# cw304_notduino_02.net
KiCad netlist of a schematic drawn in EAGLE
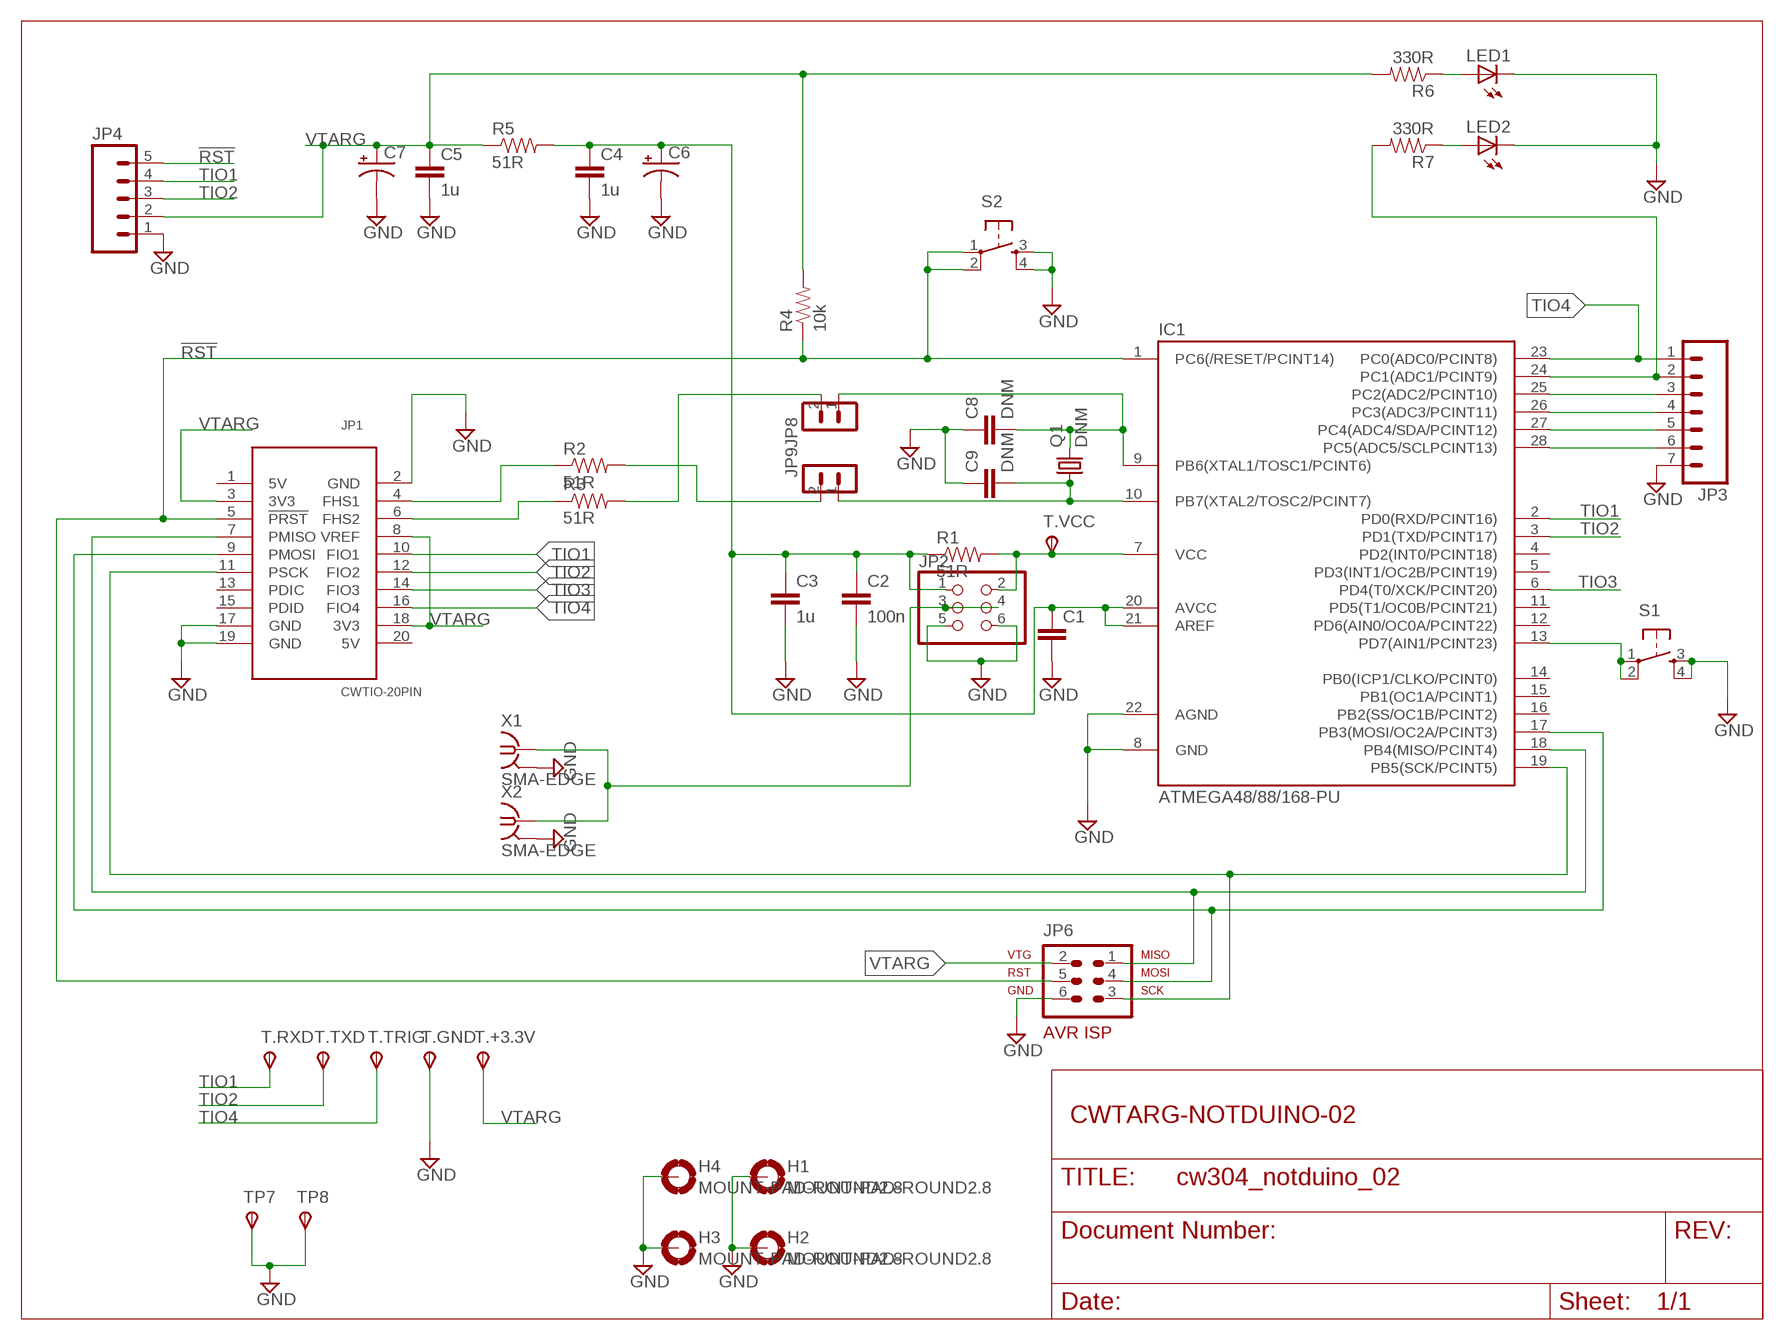
[diagram p0: schematic, sheet 1]

(export (version "E")
  (design (tool "Eeschema 10.0.6"))
  (components
    (comp (ref "C1")
      (value "CAPPTH")
      (footprint "eagle-import:CAP-PTH-SMALL")
      (libsource (lib "eagle-import") (part "CAPPTH"))
    )
    (comp (ref "C2")
      (value "100n")
      (footprint "eagle-import:CAP-PTH-SMALL")
      (libsource (lib "eagle-import") (part "CAPPTH"))
    )
    (comp (ref "C3")
      (value "1u")
      (footprint "eagle-import:CAP-PTH-SMALL")
      (libsource (lib "eagle-import") (part "CAPPTH"))
    )
    (comp (ref "C4")
      (value "1u")
      (footprint "eagle-import:CAP-PTH-SMALL")
      (libsource (lib "eagle-import") (part "CAPPTH"))
    )
    (comp (ref "C5")
      (value "1u")
      (footprint "eagle-import:CAP-PTH-SMALL")
      (libsource (lib "eagle-import") (part "CAPPTH"))
    )
    (comp (ref "C6")
      (value "CAP_POLPTH1")
      (footprint "eagle-import:CPOL-RADIAL-100UF-25V")
      (libsource (lib "eagle-import") (part "CAP_POLPTH1"))
    )
    (comp (ref "C7")
      (value "CAP_POLPTH1")
      (footprint "eagle-import:CPOL-RADIAL-100UF-25V")
      (libsource (lib "eagle-import") (part "CAP_POLPTH1"))
    )
    (comp (ref "C8")
      (value "DNM")
      (footprint "eagle-import:CAP-PTH-SMALL")
      (libsource (lib "eagle-import") (part "CAPPTH"))
    )
    (comp (ref "C9")
      (value "DNM")
      (footprint "eagle-import:CAP-PTH-SMALL")
      (libsource (lib "eagle-import") (part "CAPPTH"))
    )
    (comp (ref "H1")
      (value "MOUNT-PAD-ROUND2.8")
      (footprint "eagle-import:2,8-PAD")
      (libsource (lib "eagle-import") (part "MOUNT-PAD-ROUND2.8"))
    )
    (comp (ref "H2")
      (value "MOUNT-PAD-ROUND2.8")
      (footprint "eagle-import:2,8-PAD")
      (libsource (lib "eagle-import") (part "MOUNT-PAD-ROUND2.8"))
    )
    (comp (ref "H3")
      (value "MOUNT-PAD-ROUND2.8")
      (footprint "eagle-import:2,8-PAD")
      (libsource (lib "eagle-import") (part "MOUNT-PAD-ROUND2.8"))
    )
    (comp (ref "H4")
      (value "MOUNT-PAD-ROUND2.8")
      (footprint "eagle-import:2,8-PAD")
      (libsource (lib "eagle-import") (part "MOUNT-PAD-ROUND2.8"))
    )
    (comp (ref "IC1")
      (value "ATMEGA48/88/168-PU")
      (footprint "eagle-import:DIL28-3")
      (libsource (lib "eagle-import") (part "ATMEGA48/88/168-PU"))
    )
    (comp (ref "JP1")
      (value "CWTIO-20PIN")
      (footprint "eagle-import:PINSHRD_PTH_2X10")
      (libsource (lib "eagle-import") (part "CWTIO-20PIN"))
    )
    (comp (ref "JP2")
      (value "PINHD-2X3")
      (footprint "eagle-import:2X03")
      (libsource (lib "eagle-import") (part "PINHD-2X3"))
    )
    (comp (ref "JP3")
      (value "M07LOCK")
      (footprint "eagle-import:1X07_LOCK")
      (libsource (lib "eagle-import") (part "M07LOCK"))
    )
    (comp (ref "JP4")
      (value "M05LOCK")
      (footprint "eagle-import:1X05_LOCK")
      (libsource (lib "eagle-import") (part "M05LOCK"))
    )
    (comp (ref "JP6")
      (value "AVR-ISP-6")
      (footprint "eagle-import:AVR-ISP-6")
      (libsource (lib "eagle-import") (part "AVR-ISP-6"))
    )
    (comp (ref "JP8")
      (value "M02LOCK")
      (footprint "eagle-import:1X02_LOCK")
      (libsource (lib "eagle-import") (part "M02LOCK"))
    )
    (comp (ref "JP9")
      (value "M02LOCK")
      (footprint "eagle-import:1X02_LOCK")
      (libsource (lib "eagle-import") (part "M02LOCK"))
    )
    (comp (ref "LED1")
      (value "LED5MM")
      (footprint "eagle-import:LED5MM")
      (libsource (lib "eagle-import") (part "LED5MM"))
    )
    (comp (ref "LED2")
      (value "LED5MM")
      (footprint "eagle-import:LED5MM")
      (libsource (lib "eagle-import") (part "LED5MM"))
    )
    (comp (ref "Q1")
      (value "DNM")
      (footprint "eagle-import:HC49U-V")
      (libsource (lib "eagle-import") (part "CRYSTALHC49U-V"))
    )
    (comp (ref "R1")
      (value "51R")
      (footprint "eagle-import:AXIAL-0.4")
      (libsource (lib "eagle-import") (part "RESISTORPTH-1/4W"))
    )
    (comp (ref "R2")
      (value "51R")
      (footprint "eagle-import:AXIAL-0.4")
      (libsource (lib "eagle-import") (part "RESISTORPTH-1/4W"))
    )
    (comp (ref "R3")
      (value "51R")
      (footprint "eagle-import:AXIAL-0.4")
      (libsource (lib "eagle-import") (part "RESISTORPTH-1/4W"))
    )
    (comp (ref "R4")
      (value "10k")
      (footprint "eagle-import:AXIAL-0.4")
      (libsource (lib "eagle-import") (part "RESISTORPTH-1/4W"))
    )
    (comp (ref "R5")
      (value "51R")
      (footprint "eagle-import:AXIAL-0.4")
      (libsource (lib "eagle-import") (part "RESISTORPTH-1/4W"))
    )
    (comp (ref "R6")
      (value "330R")
      (footprint "eagle-import:AXIAL-0.4")
      (libsource (lib "eagle-import") (part "RESISTORPTH-1/4W"))
    )
    (comp (ref "R7")
      (value "330R")
      (footprint "eagle-import:AXIAL-0.4")
      (libsource (lib "eagle-import") (part "RESISTORPTH-1/4W"))
    )
    (comp (ref "S1")
      (value "TAC_SWITCHPTH")
      (footprint "eagle-import:TACTILE-PTH")
      (libsource (lib "eagle-import") (part "TAC_SWITCHPTH"))
    )
    (comp (ref "S2")
      (value "TAC_SWITCHPTH")
      (footprint "eagle-import:TACTILE-PTH")
      (libsource (lib "eagle-import") (part "TAC_SWITCHPTH"))
    )
    (comp (ref "T.+3.3V")
      (value "TPSPAD1-13")
      (footprint "eagle-import:P1-13")
      (libsource (lib "eagle-import") (part "TPSPAD1-13"))
    )
    (comp (ref "T.GND")
      (value "TPSPAD1-13")
      (footprint "eagle-import:P1-13")
      (libsource (lib "eagle-import") (part "TPSPAD1-13"))
    )
    (comp (ref "T.RXD")
      (value "TPSPAD1-13")
      (footprint "eagle-import:P1-13")
      (libsource (lib "eagle-import") (part "TPSPAD1-13"))
    )
    (comp (ref "T.TRIG")
      (value "TPSPAD1-13")
      (footprint "eagle-import:P1-13")
      (libsource (lib "eagle-import") (part "TPSPAD1-13"))
    )
    (comp (ref "T.TXD")
      (value "TPSPAD1-13")
      (footprint "eagle-import:P1-13")
      (libsource (lib "eagle-import") (part "TPSPAD1-13"))
    )
    (comp (ref "T.VCC")
      (value "TPSPAD1-17")
      (footprint "eagle-import:P1-17")
      (libsource (lib "eagle-import") (part "TPSPAD1-17"))
    )
    (comp (ref "TP7")
      (value "TPSPAD1-17")
      (footprint "eagle-import:P1-17")
      (libsource (lib "eagle-import") (part "TPSPAD1-17"))
    )
    (comp (ref "TP8")
      (value "TPSPAD1-17")
      (footprint "eagle-import:P1-17")
      (libsource (lib "eagle-import") (part "TPSPAD1-17"))
    )
    (comp (ref "X1")
      (value "SMA-EDGE")
      (footprint "eagle-import:J502-ND-142-0711-821_826")
      (fields (field (name "MF") "JOHNSON COMPONENTS") (field (name "MPN") "142-0711-821"))
      (libsource (lib "eagle-import") (part "SMA-EDGE"))
    )
    (comp (ref "X2")
      (value "SMA-EDGE")
      (footprint "eagle-import:J502-ND-142-0711-821_826")
      (fields (field (name "MF") "JOHNSON COMPONENTS") (field (name "MPN") "142-0711-821"))
      (libsource (lib "eagle-import") (part "SMA-EDGE"))
    )
  )
  (nets
    (net (code "1") (name "/~{RST}") (class "Default")
      (node (ref "IC1") (pin "1") (pinfunction "PC6(/RESET/PCINT14)_1") (pintype "bidirectional"))
      (node (ref "JP1") (pin "5") (pinfunction "~{PRST}_5") (pintype "bidirectional"))
      (node (ref "JP4") (pin "5") (pinfunction "5_5") (pintype "passive"))
      (node (ref "JP6") (pin "5") (pinfunction "5_5") (pintype "passive"))
      (node (ref "R4") (pin "P$1") (pinfunction "1_P$1") (pintype "passive"))
      (node (ref "S2") (pin "1") (pinfunction "1_1") (pintype "passive"))
      (node (ref "S2") (pin "2") (pinfunction "2_2") (pintype "passive"))
    )
    (net (code "2") (name "GND") (class "Default")
      (node (ref "C1") (pin "2") (pinfunction "2_2") (pintype "passive"))
      (node (ref "C2") (pin "2") (pinfunction "2_2") (pintype "passive"))
      (node (ref "C3") (pin "2") (pinfunction "2_2") (pintype "passive"))
      (node (ref "C4") (pin "2") (pinfunction "2_2") (pintype "passive"))
      (node (ref "C5") (pin "2") (pinfunction "2_2") (pintype "passive"))
      (node (ref "C6") (pin "2") (pinfunction "-_2") (pintype "passive"))
      (node (ref "C7") (pin "2") (pinfunction "-_2") (pintype "passive"))
      (node (ref "C8") (pin "1") (pinfunction "1_1") (pintype "passive"))
      (node (ref "C9") (pin "1") (pinfunction "1_1") (pintype "passive"))
      (node (ref "H1") (pin "B2,8") (pinfunction "MOUNT_B2,8") (pintype "passive"))
      (node (ref "H2") (pin "B2,8") (pinfunction "MOUNT_B2,8") (pintype "passive"))
      (node (ref "H3") (pin "B2,8") (pinfunction "MOUNT_B2,8") (pintype "passive"))
      (node (ref "H4") (pin "B2,8") (pinfunction "MOUNT_B2,8") (pintype "passive"))
      (node (ref "IC1") (pin "22") (pinfunction "AGND_22") (pintype "power_in"))
      (node (ref "IC1") (pin "8") (pinfunction "GND_8") (pintype "power_in"))
      (node (ref "JP1") (pin "17") (pinfunction "GND_17") (pintype "bidirectional"))
      (node (ref "JP1") (pin "19") (pinfunction "GND_19") (pintype "bidirectional"))
      (node (ref "JP1") (pin "2") (pinfunction "GND_2") (pintype "bidirectional"))
      (node (ref "JP2") (pin "5") (pinfunction "5_5") (pintype "passive"))
      (node (ref "JP2") (pin "6") (pinfunction "6_6") (pintype "passive"))
      (node (ref "JP3") (pin "7") (pinfunction "7_7") (pintype "passive"))
      (node (ref "JP4") (pin "1") (pinfunction "1_1") (pintype "passive"))
      (node (ref "JP6") (pin "6") (pinfunction "6_6") (pintype "passive"))
      (node (ref "LED1") (pin "K") (pinfunction "C_K") (pintype "passive"))
      (node (ref "LED2") (pin "K") (pinfunction "C_K") (pintype "passive"))
      (node (ref "S1") (pin "3") (pinfunction "3_3") (pintype "passive"))
      (node (ref "S1") (pin "4") (pinfunction "4_4") (pintype "passive"))
      (node (ref "S2") (pin "3") (pinfunction "3_3") (pintype "passive"))
      (node (ref "S2") (pin "4") (pinfunction "4_4") (pintype "passive"))
      (node (ref "T.GND") (pin "TP") (pinfunction "PP_TP") (pintype "input"))
      (node (ref "TP7") (pin "TP") (pinfunction "PP_TP") (pintype "input"))
      (node (ref "TP8") (pin "TP") (pinfunction "PP_TP") (pintype "input"))
      (node (ref "X1") (pin "G@1") (pinfunction "2_G@1") (pintype "passive"))
      (node (ref "X1") (pin "G@2") (pinfunction "2_G@2") (pintype "passive"))
      (node (ref "X1") (pin "G@3") (pinfunction "2_G@3") (pintype "passive"))
      (node (ref "X1") (pin "G@4") (pinfunction "2_G@4") (pintype "passive"))
      (node (ref "X2") (pin "G@1") (pinfunction "2_G@1") (pintype "passive"))
      (node (ref "X2") (pin "G@2") (pinfunction "2_G@2") (pintype "passive"))
      (node (ref "X2") (pin "G@3") (pinfunction "2_G@3") (pintype "passive"))
      (node (ref "X2") (pin "G@4") (pinfunction "2_G@4") (pintype "passive"))
    )
    (net (code "3") (name "Net-(C6-+)") (class "Default")
      (node (ref "C1") (pin "1") (pinfunction "1_1") (pintype "passive"))
      (node (ref "C2") (pin "1") (pinfunction "1_1") (pintype "passive"))
      (node (ref "C3") (pin "1") (pinfunction "1_1") (pintype "passive"))
      (node (ref "C4") (pin "1") (pinfunction "1_1") (pintype "passive"))
      (node (ref "C6") (pin "1") (pinfunction "+_1") (pintype "passive"))
      (node (ref "IC1") (pin "20") (pinfunction "AVCC_20") (pintype "passive"))
      (node (ref "IC1") (pin "21") (pinfunction "AREF_21") (pintype "passive"))
      (node (ref "JP2") (pin "1") (pinfunction "1_1") (pintype "passive"))
      (node (ref "R1") (pin "P$1") (pinfunction "1_P$1") (pintype "passive"))
      (node (ref "R5") (pin "P$2") (pinfunction "2_P$2") (pintype "passive"))
    )
    (net (code "4") (name "Net-(IC1-PB3(MOSI{slash}OC2A{slash}PCINT3))") (class "Default")
      (node (ref "IC1") (pin "17") (pinfunction "PB3(MOSI/OC2A/PCINT3)_17") (pintype "bidirectional"))
      (node (ref "JP1") (pin "9") (pinfunction "PMOSI_9") (pintype "bidirectional"))
      (node (ref "JP6") (pin "4") (pinfunction "4_4") (pintype "passive"))
    )
    (net (code "5") (name "Net-(IC1-PB4(MISO{slash}PCINT4))") (class "Default")
      (node (ref "IC1") (pin "18") (pinfunction "PB4(MISO/PCINT4)_18") (pintype "bidirectional"))
      (node (ref "JP1") (pin "7") (pinfunction "PMISO_7") (pintype "bidirectional"))
      (node (ref "JP6") (pin "1") (pinfunction "1_1") (pintype "passive"))
    )
    (net (code "6") (name "Net-(IC1-PB5(SCK{slash}PCINT5))") (class "Default")
      (node (ref "IC1") (pin "19") (pinfunction "PB5(SCK/PCINT5)_19") (pintype "bidirectional"))
      (node (ref "JP1") (pin "11") (pinfunction "PSCK_11") (pintype "bidirectional"))
      (node (ref "JP6") (pin "3") (pinfunction "3_3") (pintype "passive"))
    )
    (net (code "7") (name "Net-(IC1-PB6(XTAL1{slash}TOSC1{slash}PCINT6))") (class "Default")
      (node (ref "C8") (pin "2") (pinfunction "2_2") (pintype "passive"))
      (node (ref "IC1") (pin "9") (pinfunction "PB6(XTAL1/TOSC1/PCINT6)_9") (pintype "bidirectional"))
      (node (ref "JP8") (pin "1") (pinfunction "1_1") (pintype "passive"))
      (node (ref "Q1") (pin "2") (pinfunction "2_2") (pintype "passive"))
    )
    (net (code "8") (name "Net-(IC1-PB7(XTAL2{slash}TOSC2{slash}PCINT7))") (class "Default")
      (node (ref "C9") (pin "2") (pinfunction "2_2") (pintype "passive"))
      (node (ref "IC1") (pin "10") (pinfunction "PB7(XTAL2/TOSC2/PCINT7)_10") (pintype "bidirectional"))
      (node (ref "JP9") (pin "1") (pinfunction "1_1") (pintype "passive"))
      (node (ref "Q1") (pin "1") (pinfunction "1_1") (pintype "passive"))
    )
    (net (code "9") (name "Net-(IC1-PC1(ADC1{slash}PCINT9))") (class "Default")
      (node (ref "IC1") (pin "24") (pinfunction "PC1(ADC1/PCINT9)_24") (pintype "bidirectional"))
      (node (ref "JP3") (pin "2") (pinfunction "2_2") (pintype "passive"))
      (node (ref "R7") (pin "P$2") (pinfunction "2_P$2") (pintype "passive"))
    )
    (net (code "10") (name "Net-(IC1-PC2(ADC2{slash}PCINT10))") (class "Default")
      (node (ref "IC1") (pin "25") (pinfunction "PC2(ADC2/PCINT10)_25") (pintype "bidirectional"))
      (node (ref "JP3") (pin "3") (pinfunction "3_3") (pintype "passive"))
    )
    (net (code "11") (name "Net-(IC1-PC3(ADC3{slash}PCINT11))") (class "Default")
      (node (ref "IC1") (pin "26") (pinfunction "PC3(ADC3/PCINT11)_26") (pintype "bidirectional"))
      (node (ref "JP3") (pin "4") (pinfunction "4_4") (pintype "passive"))
    )
    (net (code "12") (name "Net-(IC1-PC4(ADC4{slash}SDA{slash}PCINT12))") (class "Default")
      (node (ref "IC1") (pin "27") (pinfunction "PC4(ADC4/SDA/PCINT12)_27") (pintype "bidirectional"))
      (node (ref "JP3") (pin "5") (pinfunction "5_5") (pintype "passive"))
    )
    (net (code "13") (name "Net-(IC1-PC5(ADC5{slash}SCLPCINT13))") (class "Default")
      (node (ref "IC1") (pin "28") (pinfunction "PC5(ADC5/SCLPCINT13)_28") (pintype "bidirectional"))
      (node (ref "JP3") (pin "6") (pinfunction "6_6") (pintype "passive"))
    )
    (net (code "14") (name "Net-(IC1-PD7(AIN1{slash}PCINT23))") (class "Default")
      (node (ref "IC1") (pin "13") (pinfunction "PD7(AIN1/PCINT23)_13") (pintype "bidirectional"))
      (node (ref "S1") (pin "1") (pinfunction "1_1") (pintype "passive"))
      (node (ref "S1") (pin "2") (pinfunction "2_2") (pintype "passive"))
    )
    (net (code "15") (name "Net-(IC1-VCC)") (class "Default")
      (node (ref "IC1") (pin "7") (pinfunction "VCC_7") (pintype "power_in"))
      (node (ref "JP2") (pin "2") (pinfunction "2_2") (pintype "passive"))
      (node (ref "R1") (pin "P$2") (pinfunction "2_P$2") (pintype "passive"))
      (node (ref "T.VCC") (pin "TP") (pinfunction "PP_TP") (pintype "input"))
    )
    (net (code "16") (name "Net-(JP1-FHS1)") (class "Default")
      (node (ref "JP1") (pin "4") (pinfunction "FHS1_4") (pintype "bidirectional"))
      (node (ref "R2") (pin "P$1") (pinfunction "1_P$1") (pintype "passive"))
    )
    (net (code "17") (name "Net-(JP1-FHS2)") (class "Default")
      (node (ref "JP1") (pin "6") (pinfunction "FHS2_6") (pintype "bidirectional"))
      (node (ref "R3") (pin "P$1") (pinfunction "1_P$1") (pintype "passive"))
    )
    (net (code "18") (name "Net-(JP2-Pad3)") (class "Default")
      (node (ref "JP2") (pin "3") (pinfunction "3_3") (pintype "passive"))
      (node (ref "JP2") (pin "4") (pinfunction "4_4") (pintype "passive"))
      (node (ref "X1") (pin "1") (pinfunction "1_1") (pintype "passive"))
      (node (ref "X2") (pin "1") (pinfunction "1_1") (pintype "passive"))
    )
    (net (code "19") (name "Net-(R2-2)") (class "Default")
      (node (ref "JP9") (pin "2") (pinfunction "2_2") (pintype "passive"))
      (node (ref "R2") (pin "P$2") (pinfunction "2_P$2") (pintype "passive"))
    )
    (net (code "20") (name "Net-(R3-2)") (class "Default")
      (node (ref "JP8") (pin "2") (pinfunction "2_2") (pintype "passive"))
      (node (ref "R3") (pin "P$2") (pinfunction "2_P$2") (pintype "passive"))
    )
    (net (code "21") (name "Net-(R6-1)") (class "Default")
      (node (ref "LED1") (pin "A") (pinfunction "A_A") (pintype "passive"))
      (node (ref "R6") (pin "P$1") (pinfunction "1_P$1") (pintype "passive"))
    )
    (net (code "22") (name "Net-(R7-1)") (class "Default")
      (node (ref "LED2") (pin "A") (pinfunction "A_A") (pintype "passive"))
      (node (ref "R7") (pin "P$1") (pinfunction "1_P$1") (pintype "passive"))
    )
    (net (code "23") (name "TIO1") (class "Default")
      (node (ref "IC1") (pin "2") (pinfunction "PD0(RXD/PCINT16)_2") (pintype "bidirectional"))
      (node (ref "JP1") (pin "10") (pinfunction "FIO1_10") (pintype "bidirectional"))
      (node (ref "JP4") (pin "4") (pinfunction "4_4") (pintype "passive"))
      (node (ref "T.RXD") (pin "TP") (pinfunction "PP_TP") (pintype "input"))
    )
    (net (code "24") (name "TIO2") (class "Default")
      (node (ref "IC1") (pin "3") (pinfunction "PD1(TXD/PCINT17)_3") (pintype "bidirectional"))
      (node (ref "JP1") (pin "12") (pinfunction "FIO2_12") (pintype "bidirectional"))
      (node (ref "JP4") (pin "3") (pinfunction "3_3") (pintype "passive"))
      (node (ref "T.TXD") (pin "TP") (pinfunction "PP_TP") (pintype "input"))
    )
    (net (code "25") (name "TIO3") (class "Default")
      (node (ref "IC1") (pin "6") (pinfunction "PD4(T0/XCK/PCINT20)_6") (pintype "bidirectional"))
      (node (ref "JP1") (pin "14") (pinfunction "FIO3_14") (pintype "bidirectional"))
    )
    (net (code "26") (name "TIO4") (class "Default")
      (node (ref "IC1") (pin "23") (pinfunction "PC0(ADC0/PCINT8)_23") (pintype "bidirectional"))
      (node (ref "JP1") (pin "16") (pinfunction "FIO4_16") (pintype "bidirectional"))
      (node (ref "JP3") (pin "1") (pinfunction "1_1") (pintype "passive"))
      (node (ref "T.TRIG") (pin "TP") (pinfunction "PP_TP") (pintype "input"))
    )
    (net (code "27") (name "VTARG") (class "Default")
      (node (ref "C5") (pin "1") (pinfunction "1_1") (pintype "passive"))
      (node (ref "C7") (pin "1") (pinfunction "+_1") (pintype "passive"))
      (node (ref "JP1") (pin "18") (pinfunction "3V3_18") (pintype "bidirectional"))
      (node (ref "JP1") (pin "3") (pinfunction "3V3_3") (pintype "bidirectional"))
      (node (ref "JP1") (pin "8") (pinfunction "VREF_8") (pintype "bidirectional"))
      (node (ref "JP4") (pin "2") (pinfunction "2_2") (pintype "passive"))
      (node (ref "JP6") (pin "2") (pinfunction "2_2") (pintype "passive"))
      (node (ref "R4") (pin "P$2") (pinfunction "2_P$2") (pintype "passive"))
      (node (ref "R5") (pin "P$1") (pinfunction "1_P$1") (pintype "passive"))
      (node (ref "R6") (pin "P$2") (pinfunction "2_P$2") (pintype "passive"))
      (node (ref "T.+3.3V") (pin "TP") (pinfunction "PP_TP") (pintype "input"))
    )
    (net (code "28") (name "unconnected-(IC1-PB0(ICP1{slash}CLKO{slash}PCINT0)-Pad14)") (class "Default")
      (node (ref "IC1") (pin "14") (pinfunction "PB0(ICP1/CLKO/PCINT0)_14") (pintype "bidirectional"))
    )
    (net (code "29") (name "unconnected-(IC1-PB1(OC1A{slash}PCINT1)-Pad15)") (class "Default")
      (node (ref "IC1") (pin "15") (pinfunction "PB1(OC1A/PCINT1)_15") (pintype "bidirectional"))
    )
    (net (code "30") (name "unconnected-(IC1-PB2(SS{slash}OC1B{slash}PCINT2)-Pad16)") (class "Default")
      (node (ref "IC1") (pin "16") (pinfunction "PB2(SS/OC1B/PCINT2)_16") (pintype "bidirectional"))
    )
    (net (code "31") (name "unconnected-(IC1-PD2(INT0{slash}PCINT18)-Pad4)") (class "Default")
      (node (ref "IC1") (pin "4") (pinfunction "PD2(INT0/PCINT18)_4") (pintype "bidirectional"))
    )
    (net (code "32") (name "unconnected-(IC1-PD3(INT1{slash}OC2B{slash}PCINT19)-Pad5)") (class "Default")
      (node (ref "IC1") (pin "5") (pinfunction "PD3(INT1/OC2B/PCINT19)_5") (pintype "bidirectional"))
    )
    (net (code "33") (name "unconnected-(IC1-PD5(T1{slash}OC0B{slash}PCINT21)-Pad11)") (class "Default")
      (node (ref "IC1") (pin "11") (pinfunction "PD5(T1/OC0B/PCINT21)_11") (pintype "bidirectional"))
    )
    (net (code "34") (name "unconnected-(IC1-PD6(AIN0{slash}OC0A{slash}PCINT22)-Pad12)") (class "Default")
      (node (ref "IC1") (pin "12") (pinfunction "PD6(AIN0/OC0A/PCINT22)_12") (pintype "bidirectional"))
    )
    (net (code "35") (name "unconnected-(JP1-5V-Pad1)") (class "Default")
      (node (ref "JP1") (pin "1") (pinfunction "5V_1") (pintype "bidirectional"))
    )
    (net (code "36") (name "unconnected-(JP1-5V-Pad20)") (class "Default")
      (node (ref "JP1") (pin "20") (pinfunction "5V_20") (pintype "bidirectional"))
    )
    (net (code "37") (name "unconnected-(JP1-PDIC-Pad13)") (class "Default")
      (node (ref "JP1") (pin "13") (pinfunction "PDIC_13") (pintype "bidirectional"))
    )
    (net (code "38") (name "unconnected-(JP1-PDID-Pad15)") (class "Default")
      (node (ref "JP1") (pin "15") (pinfunction "PDID_15") (pintype "bidirectional"))
    )
  )
)
